# DC950TestSystem.net
KiCad netlist of a schematic drawn in EAGLE
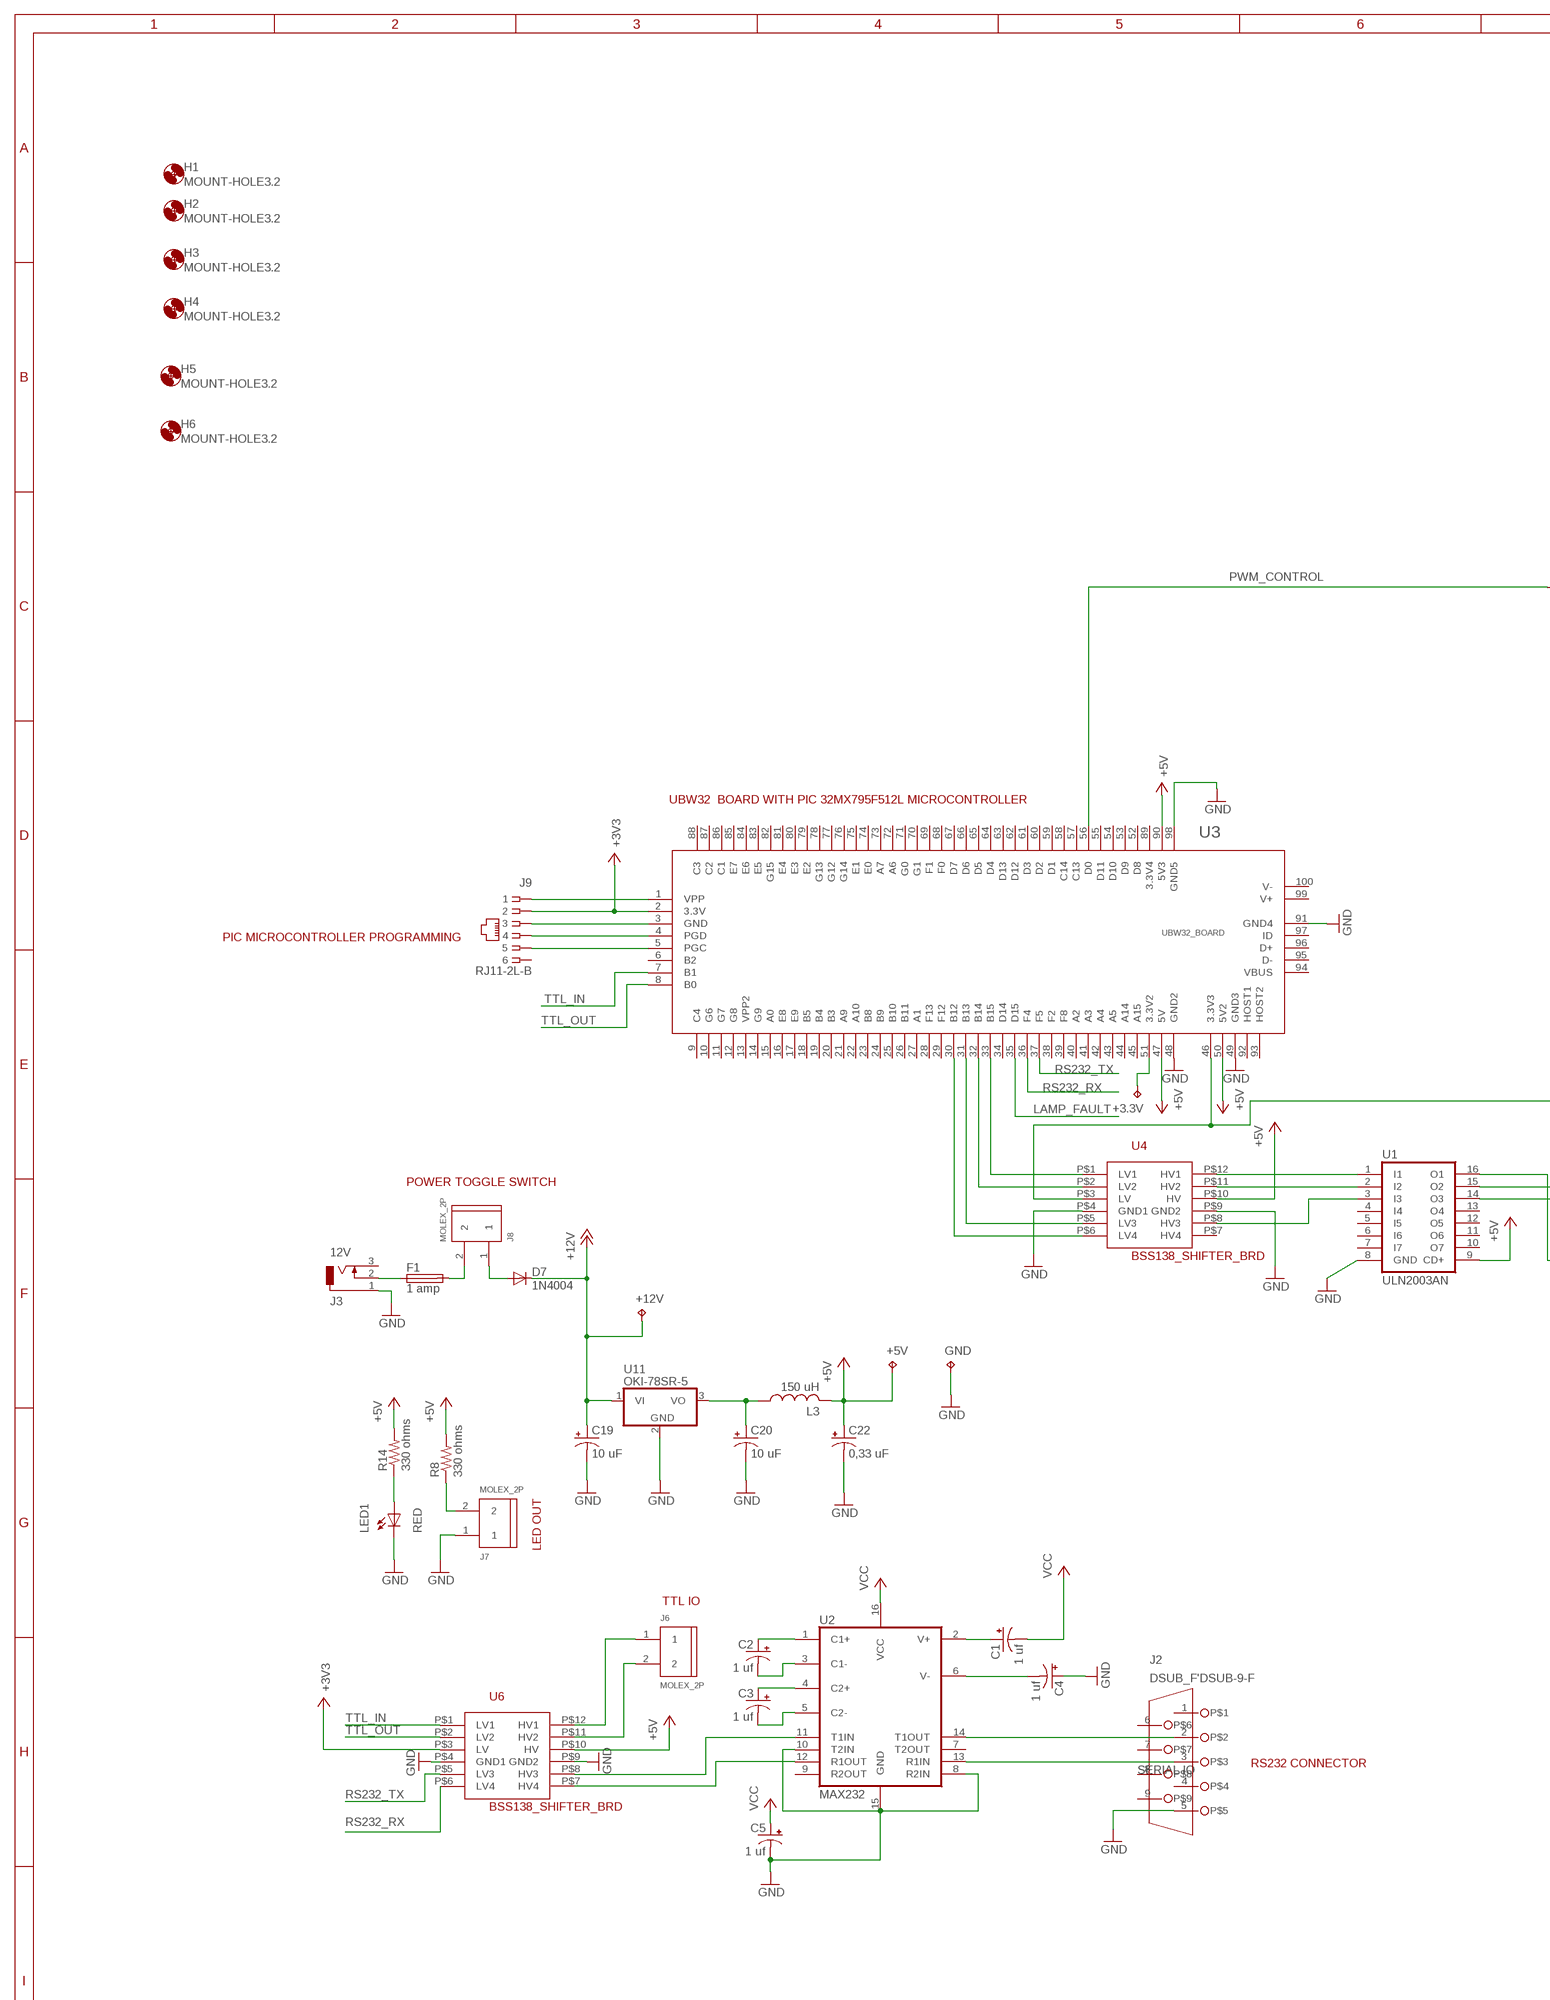
[diagram p0: schematic, sheet 1, part 1 of 2]
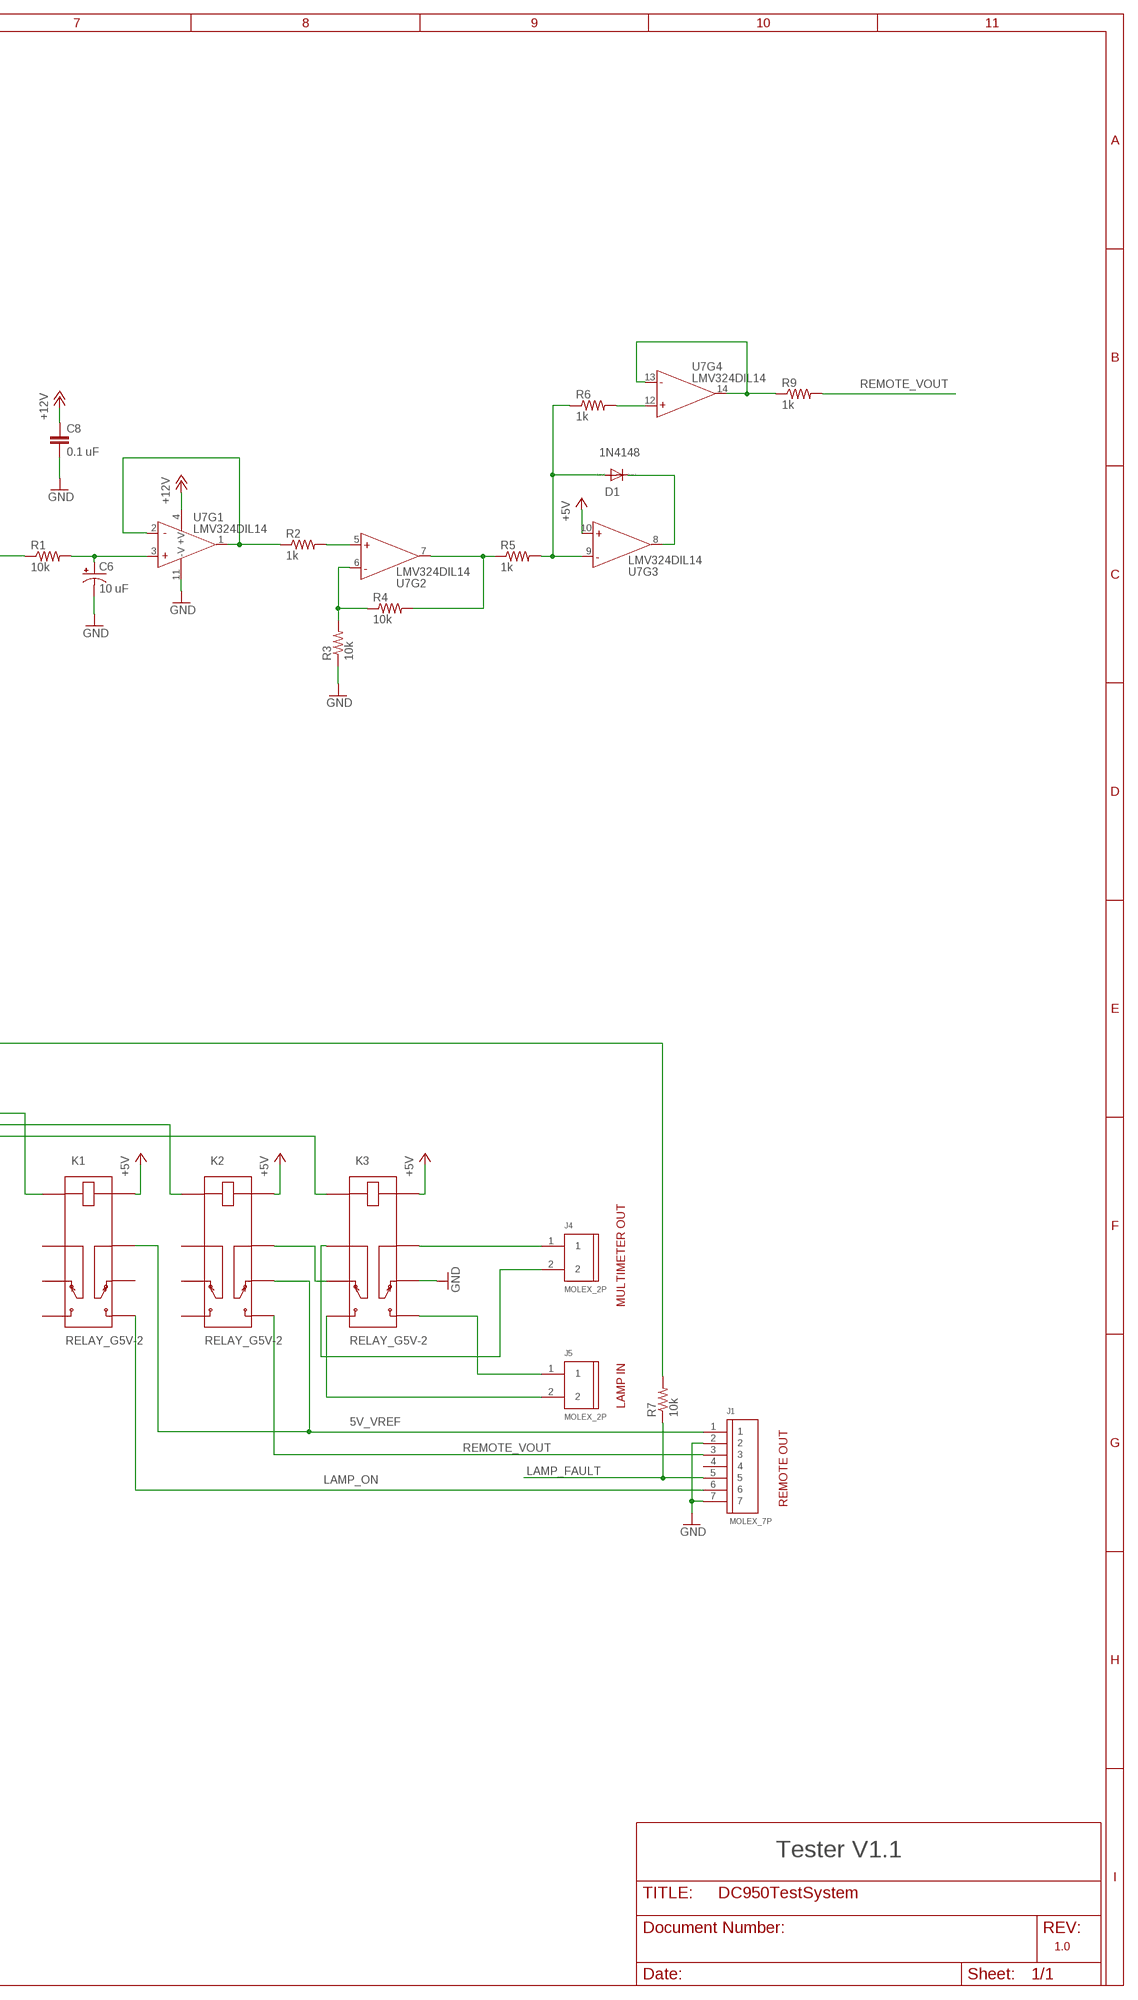
[diagram p1: schematic, sheet 1, part 2 of 2]

(export (version "E")
  (design (tool "Eeschema 10.0.6"))
  (components
    (comp (ref "+3.3V")
      (value "TP")
      (footprint "eagle-import:TESTPAD")
      (libsource (lib "eagle-import") (part "TP"))
    )
    (comp (ref "+5V")
      (value "TP")
      (footprint "eagle-import:TESTPAD")
      (libsource (lib "eagle-import") (part "TP"))
    )
    (comp (ref "+12V")
      (value "TP")
      (footprint "eagle-import:TESTPAD")
      (libsource (lib "eagle-import") (part "TP"))
    )
    (comp (ref "C1")
      (value "1 uf")
      (footprint "eagle-import:E2-5")
      (libsource (lib "eagle-import") (part "CPOL-USE2-5"))
    )
    (comp (ref "C2")
      (value "1 uf")
      (footprint "eagle-import:E2-5")
      (libsource (lib "eagle-import") (part "CPOL-USE2-5"))
    )
    (comp (ref "C3")
      (value "1 uf")
      (footprint "eagle-import:E2-5")
      (libsource (lib "eagle-import") (part "CPOL-USE2-5"))
    )
    (comp (ref "C4")
      (value "1 uf")
      (footprint "eagle-import:E2-5")
      (libsource (lib "eagle-import") (part "CPOL-USE2-5"))
    )
    (comp (ref "C5")
      (value "1 uf")
      (footprint "eagle-import:E2-5")
      (libsource (lib "eagle-import") (part "CPOL-USE2-5"))
    )
    (comp (ref "C6")
      (value "10 uF")
      (footprint "eagle-import:E2-5")
      (libsource (lib "eagle-import") (part "CPOL-USE2-5"))
    )
    (comp (ref "C8")
      (value "0.1 uF")
      (footprint "eagle-import:C5B2.5")
      (libsource (lib "eagle-import") (part "C5/2.5"))
    )
    (comp (ref "C19")
      (value "10 uF")
      (footprint "eagle-import:E2-5")
      (libsource (lib "eagle-import") (part "CPOL-USE2-5"))
    )
    (comp (ref "C20")
      (value "10 uF")
      (footprint "eagle-import:E2-5")
      (libsource (lib "eagle-import") (part "CPOL-USE2-5"))
    )
    (comp (ref "C22")
      (value "0,33 uF")
      (footprint "eagle-import:E2-5")
      (libsource (lib "eagle-import") (part "CPOL-USE2-5"))
    )
    (comp (ref "D1")
      (value "1N4148")
      (footprint "eagle-import:DO35-10")
      (libsource (lib "eagle-import") (part "1N4148DO35-10"))
    )
    (comp (ref "D7")
      (value "1N4004")
      (footprint "eagle-import:DO41-10")
      (libsource (lib "eagle-import") (part "1N4004"))
    )
    (comp (ref "F1")
      (value "1 amp")
      (footprint "eagle-import:SH22,5")
      (fields (field (name "MF") "SCHURTER") (field (name "MPN") "0031.8201"))
      (libsource (lib "eagle-import") (part "SH22,5"))
    )
    (comp (ref "GND")
      (value "TP")
      (footprint "eagle-import:TESTPAD")
      (libsource (lib "eagle-import") (part "TP"))
    )
    (comp (ref "H1")
      (value "MOUNT-HOLE3.2")
      (footprint "eagle-import:3,2")
      (libsource (lib "eagle-import") (part "MOUNT-HOLE3.2"))
    )
    (comp (ref "H2")
      (value "MOUNT-HOLE3.2")
      (footprint "eagle-import:3,2")
      (libsource (lib "eagle-import") (part "MOUNT-HOLE3.2"))
    )
    (comp (ref "H3")
      (value "MOUNT-HOLE3.2")
      (footprint "eagle-import:3,2")
      (libsource (lib "eagle-import") (part "MOUNT-HOLE3.2"))
    )
    (comp (ref "H4")
      (value "MOUNT-HOLE3.2")
      (footprint "eagle-import:3,2")
      (libsource (lib "eagle-import") (part "MOUNT-HOLE3.2"))
    )
    (comp (ref "H5")
      (value "MOUNT-HOLE3.2")
      (footprint "eagle-import:3,2")
      (libsource (lib "eagle-import") (part "MOUNT-HOLE3.2"))
    )
    (comp (ref "H6")
      (value "MOUNT-HOLE3.2")
      (footprint "eagle-import:3,2")
      (libsource (lib "eagle-import") (part "MOUNT-HOLE3.2"))
    )
    (comp (ref "J1")
      (value "MOLEX_7P")
      (footprint "eagle-import:MOLEX_7P")
      (libsource (lib "eagle-import") (part "MOLEX_7P"))
    )
    (comp (ref "J2")
      (value "DSUB_F'DSUB-9-F")
      (footprint "eagle-import:H5M09RA")
      (libsource (lib "eagle-import") (part "DSUB_F'DSUB-9-F"))
    )
    (comp (ref "J3")
      (value "12V")
      (footprint "eagle-import:DCJ0303")
      (libsource (lib "eagle-import") (part "DCJ0303"))
    )
    (comp (ref "J4")
      (value "MOLEX_2P")
      (footprint "eagle-import:MOLEX_2P")
      (libsource (lib "eagle-import") (part "MOLEX_2P"))
    )
    (comp (ref "J5")
      (value "MOLEX_2P")
      (footprint "eagle-import:MOLEX_2P")
      (libsource (lib "eagle-import") (part "MOLEX_2P"))
    )
    (comp (ref "J6")
      (value "MOLEX_2P")
      (footprint "eagle-import:MOLEX_2P")
      (libsource (lib "eagle-import") (part "MOLEX_2P"))
    )
    (comp (ref "J7")
      (value "MOLEX_2P")
      (footprint "eagle-import:MOLEX_2P")
      (libsource (lib "eagle-import") (part "MOLEX_2P"))
    )
    (comp (ref "J8")
      (value "MOLEX_2P")
      (footprint "eagle-import:MOLEX_2P")
      (libsource (lib "eagle-import") (part "MOLEX_2P"))
    )
    (comp (ref "J9")
      (value "RJ11-2L-B")
      (footprint "eagle-import:RJ11-NO_SHIELD")
      (fields (field (name "MF") "TYCO ELECTRONICS"))
      (libsource (lib "eagle-import") (part "RJ11-2L-B"))
    )
    (comp (ref "K1")
      (value "RELAY_G5V-2")
      (footprint "eagle-import:RELAY_G5V-2")
      (libsource (lib "eagle-import") (part "RELAY_G5V-2"))
    )
    (comp (ref "K2")
      (value "RELAY_G5V-2")
      (footprint "eagle-import:RELAY_G5V-2")
      (libsource (lib "eagle-import") (part "RELAY_G5V-2"))
    )
    (comp (ref "K3")
      (value "RELAY_G5V-2")
      (footprint "eagle-import:RELAY_G5V-2")
      (libsource (lib "eagle-import") (part "RELAY_G5V-2"))
    )
    (comp (ref "L3")
      (value "150 uH")
      (footprint "eagle-import:0204_7")
      (libsource (lib "eagle-import") (part "L-US0204/7"))
    )
    (comp (ref "LED1")
      (value "RED")
      (footprint "eagle-import:LED5MM")
      (libsource (lib "eagle-import") (part "LED5MM"))
    )
    (comp (ref "R1")
      (value "10k")
      (footprint "eagle-import:1_4_WATT")
      (libsource (lib "eagle-import") (part "RESISTOR0207/12"))
    )
    (comp (ref "R2")
      (value "1k")
      (footprint "eagle-import:1_4_WATT")
      (libsource (lib "eagle-import") (part "RESISTOR0207/12"))
    )
    (comp (ref "R3")
      (value "10k")
      (footprint "eagle-import:1_4_WATT")
      (libsource (lib "eagle-import") (part "RESISTOR0207/12"))
    )
    (comp (ref "R4")
      (value "10k")
      (footprint "eagle-import:1_4_WATT")
      (libsource (lib "eagle-import") (part "RESISTOR0207/12"))
    )
    (comp (ref "R5")
      (value "1k")
      (footprint "eagle-import:1_4_WATT")
      (libsource (lib "eagle-import") (part "RESISTOR0207/12"))
    )
    (comp (ref "R6")
      (value "1k")
      (footprint "eagle-import:1_4_WATT")
      (libsource (lib "eagle-import") (part "RESISTOR0207/12"))
    )
    (comp (ref "R7")
      (value "10k")
      (footprint "eagle-import:1_4_WATT")
      (libsource (lib "eagle-import") (part "RESISTOR0207/12"))
    )
    (comp (ref "R8")
      (value "330 ohms")
      (footprint "eagle-import:0207_10")
      (libsource (lib "eagle-import") (part "R-US_0207/10"))
    )
    (comp (ref "R9")
      (value "1k")
      (footprint "eagle-import:1_4_WATT")
      (libsource (lib "eagle-import") (part "RESISTOR0207/12"))
    )
    (comp (ref "R14")
      (value "330 ohms")
      (footprint "eagle-import:0207_10")
      (libsource (lib "eagle-import") (part "R-US_0207/10"))
    )
    (comp (ref "U1")
      (value "ULN2003AN")
      (footprint "eagle-import:DIL16")
      (libsource (lib "eagle-import") (part "ULN2003AN"))
    )
    (comp (ref "U2")
      (value "MAX232")
      (footprint "eagle-import:DIL16")
      (fields (field (name "MF") "MAXIM") (field (name "MPN") "MAX232ACPE+"))
      (libsource (lib "eagle-import") (part "MAX232"))
    )
    (comp (ref "U3")
      (value "UBW32_BOARD")
      (footprint "eagle-import:UBW32")
      (libsource (lib "eagle-import") (part "UBW32_BOARD"))
    )
    (comp (ref "U4")
      (value "BSS138_SHIFTER_BRD")
      (footprint "eagle-import:BSS138_SHIFTER_BRD")
      (libsource (lib "eagle-import") (part "BSS138_SHIFTER_BRD"))
    )
    (comp (ref "U6")
      (value "BSS138_SHIFTER_BRD")
      (footprint "eagle-import:BSS138_SHIFTER_BRD")
      (libsource (lib "eagle-import") (part "BSS138_SHIFTER_BRD"))
    )
    (comp (ref "U7")
      (value "LMV324DIL14")
      (footprint "eagle-import:DIL14")
      (libsource (lib "eagle-import") (part "LMV324DIL14"))
    )
    (comp (ref "U11")
      (value "OKI-78SR-5")
      (footprint "eagle-import:TO220V")
      (libsource (lib "eagle-import") (part "78TV05"))
    )
  )
  (nets
    (net (code "1") (name "+3V3") (class "Default")
      (node (ref "J9") (pin "2") (pinfunction "2_2") (pintype "passive"))
      (node (ref "U3") (pin "2") (pinfunction "3.3V_2") (pintype "power_in"))
      (node (ref "U6") (pin "P$3") (pinfunction "LV_P$3") (pintype "bidirectional"))
    )
    (net (code "2") (name "+5V") (class "Default")
      (node (ref "+5V") (pin "P$1") (pinfunction "TP_P$1") (pintype "input"))
      (node (ref "C22") (pin "+") (pinfunction "+_+") (pintype "passive"))
      (node (ref "K1") (pin "16") (pinfunction "16_16") (pintype "bidirectional"))
      (node (ref "K2") (pin "16") (pinfunction "16_16") (pintype "bidirectional"))
      (node (ref "K3") (pin "16") (pinfunction "16_16") (pintype "bidirectional"))
      (node (ref "L3") (pin "2") (pinfunction "2_2") (pintype "passive"))
      (node (ref "R14") (pin "2") (pinfunction "2_2") (pintype "passive"))
      (node (ref "R8") (pin "2") (pinfunction "2_2") (pintype "passive"))
      (node (ref "U1") (pin "9") (pinfunction "CD+_9") (pintype "passive"))
      (node (ref "U3") (pin "47") (pinfunction "5V_47") (pintype "power_in"))
      (node (ref "U3") (pin "50") (pinfunction "5V2_50") (pintype "power_in"))
      (node (ref "U3") (pin "90") (pinfunction "5V3_90") (pintype "power_in"))
      (node (ref "U4") (pin "P$10") (pinfunction "HV_P$10") (pintype "bidirectional"))
      (node (ref "U6") (pin "P$10") (pinfunction "HV_P$10") (pintype "bidirectional"))
      (node (ref "U7") (pin "10") (pinfunction "+IN_10") (pintype "input"))
    )
    (net (code "3") (name "+12V") (class "Default")
      (node (ref "+12V") (pin "P$1") (pinfunction "TP_P$1") (pintype "input"))
      (node (ref "C19") (pin "+") (pinfunction "+_+") (pintype "passive"))
      (node (ref "C8") (pin "1") (pinfunction "1_1") (pintype "passive"))
      (node (ref "D7") (pin "C") (pinfunction "C_C") (pintype "passive"))
      (node (ref "U11") (pin "1") (pinfunction "VI_1") (pintype "input"))
      (node (ref "U7") (pin "4") (pinfunction "+V_4") (pintype "power_in"))
    )
    (net (code "4") (name "/3.3V4") (class "Default")
      (node (ref "U3") (pin "89") (pinfunction "3.3V4_89") (pintype "power_in"))
    )
    (net (code "5") (name "/5V_VREF") (class "Default")
      (node (ref "J1") (pin "1") (pinfunction "1_1") (pintype "bidirectional"))
      (node (ref "K1") (pin "13") (pinfunction "13_13") (pintype "bidirectional"))
      (node (ref "K2") (pin "11") (pinfunction "11_11") (pintype "bidirectional"))
    )
    (net (code "6") (name "/LAMP_FAULT") (class "Default")
      (node (ref "J1") (pin "5") (pinfunction "5_5") (pintype "bidirectional"))
      (node (ref "R7") (pin "1") (pinfunction "1_1") (pintype "passive"))
      (node (ref "U3") (pin "35") (pinfunction "D15_35") (pintype "bidirectional"))
    )
    (net (code "7") (name "/LAMP_ON") (class "Default")
      (node (ref "J1") (pin "6") (pinfunction "6_6") (pintype "bidirectional"))
      (node (ref "K1") (pin "9") (pinfunction "9_9") (pintype "bidirectional"))
    )
    (net (code "8") (name "/PWM_CONTROL") (class "Default")
      (node (ref "R1") (pin "1") (pinfunction "1_1") (pintype "passive"))
      (node (ref "U3") (pin "56") (pinfunction "D0_56") (pintype "bidirectional"))
    )
    (net (code "9") (name "/REMOTE_VOUT") (class "Default")
      (node (ref "J1") (pin "3") (pinfunction "3_3") (pintype "bidirectional"))
      (node (ref "K2") (pin "9") (pinfunction "9_9") (pintype "bidirectional"))
      (node (ref "R9") (pin "2") (pinfunction "2_2") (pintype "passive"))
    )
    (net (code "10") (name "/RS232_RX") (class "Default")
      (node (ref "U3") (pin "36") (pinfunction "F4_36") (pintype "bidirectional"))
      (node (ref "U6") (pin "P$6") (pinfunction "LV4_P$6") (pintype "bidirectional"))
    )
    (net (code "11") (name "/RS232_TX") (class "Default")
      (node (ref "U3") (pin "37") (pinfunction "F5_37") (pintype "bidirectional"))
      (node (ref "U6") (pin "P$5") (pinfunction "LV3_P$5") (pintype "bidirectional"))
    )
    (net (code "12") (name "/TTL_IN") (class "Default")
      (node (ref "U3") (pin "7") (pinfunction "B1_7") (pintype "bidirectional"))
      (node (ref "U6") (pin "P$1") (pinfunction "LV1_P$1") (pintype "bidirectional"))
    )
    (net (code "13") (name "/TTL_OUT") (class "Default")
      (node (ref "U3") (pin "8") (pinfunction "B0_8") (pintype "bidirectional"))
      (node (ref "U6") (pin "P$2") (pinfunction "LV2_P$2") (pintype "bidirectional"))
    )
    (net (code "14") (name "/V+") (class "Default")
      (node (ref "U3") (pin "99") (pinfunction "V+_99") (pintype "power_in"))
    )
    (net (code "15") (name "/V-") (class "Default")
      (node (ref "U3") (pin "100") (pinfunction "V-_100") (pintype "power_in"))
    )
    (net (code "16") (name "/VBUS") (class "Default")
      (node (ref "U3") (pin "94") (pinfunction "VBUS_94") (pintype "power_in"))
    )
    (net (code "17") (name "GND") (class "Default")
      (node (ref "C19") (pin "-") (pinfunction "-_-") (pintype "passive"))
      (node (ref "C20") (pin "-") (pinfunction "-_-") (pintype "passive"))
      (node (ref "C22") (pin "-") (pinfunction "-_-") (pintype "passive"))
      (node (ref "C4") (pin "+") (pinfunction "+_+") (pintype "passive"))
      (node (ref "C5") (pin "-") (pinfunction "-_-") (pintype "passive"))
      (node (ref "C6") (pin "-") (pinfunction "-_-") (pintype "passive"))
      (node (ref "C8") (pin "2") (pinfunction "2_2") (pintype "passive"))
      (node (ref "GND") (pin "P$1") (pinfunction "TP_P$1") (pintype "input"))
      (node (ref "J1") (pin "2") (pinfunction "2_2") (pintype "bidirectional"))
      (node (ref "J1") (pin "7") (pinfunction "7_7") (pintype "bidirectional"))
      (node (ref "J2") (pin "5") (pinfunction "P$5_5") (pintype "bidirectional"))
      (node (ref "J3") (pin "1") (pinfunction "1_1") (pintype "passive"))
      (node (ref "J7") (pin "1") (pinfunction "1_1") (pintype "bidirectional"))
      (node (ref "K3") (pin "11") (pinfunction "11_11") (pintype "bidirectional"))
      (node (ref "LED1") (pin "K") (pinfunction "C_K") (pintype "passive"))
      (node (ref "R3") (pin "1") (pinfunction "1_1") (pintype "passive"))
      (node (ref "U1") (pin "8") (pinfunction "GND_8") (pintype "power_in"))
      (node (ref "U11") (pin "2") (pinfunction "GND_2") (pintype "passive"))
      (node (ref "U2") (pin "10") (pinfunction "T2IN_10") (pintype "input"))
      (node (ref "U2") (pin "15") (pinfunction "GND_15") (pintype "bidirectional"))
      (node (ref "U2") (pin "8") (pinfunction "R2IN_8") (pintype "input"))
      (node (ref "U3") (pin "48") (pinfunction "GND2_48") (pintype "power_in"))
      (node (ref "U3") (pin "49") (pinfunction "GND3_49") (pintype "power_in"))
      (node (ref "U3") (pin "91") (pinfunction "GND4_91") (pintype "power_in"))
      (node (ref "U3") (pin "98") (pinfunction "GND5_98") (pintype "power_in"))
      (node (ref "U4") (pin "P$4") (pinfunction "GND1_P$4") (pintype "bidirectional"))
      (node (ref "U4") (pin "P$9") (pinfunction "GND2_P$9") (pintype "bidirectional"))
      (node (ref "U6") (pin "P$4") (pinfunction "GND1_P$4") (pintype "bidirectional"))
      (node (ref "U6") (pin "P$9") (pinfunction "GND2_P$9") (pintype "bidirectional"))
      (node (ref "U7") (pin "11") (pinfunction "-V_11") (pintype "power_in"))
    )
    (net (code "18") (name "Net-(+3.3V-TP)") (class "Default")
      (node (ref "+3.3V") (pin "P$1") (pinfunction "TP_P$1") (pintype "input"))
      (node (ref "U3") (pin "51") (pinfunction "3.3V2_51") (pintype "power_in"))
    )
    (net (code "19") (name "Net-(D7-PadA)") (class "Default")
      (node (ref "D7") (pin "A") (pinfunction "A_A") (pintype "passive"))
      (node (ref "J8") (pin "1") (pinfunction "1_1") (pintype "bidirectional"))
    )
    (net (code "20") (name "Net-(F1-Pad1)") (class "Default")
      (node (ref "F1") (pin "1") (pinfunction "1_1") (pintype "passive"))
      (node (ref "J3") (pin "2") (pinfunction "2_2") (pintype "passive"))
    )
    (net (code "21") (name "Net-(F1-Pad2)") (class "Default")
      (node (ref "F1") (pin "2") (pinfunction "2_2") (pintype "passive"))
      (node (ref "J8") (pin "2") (pinfunction "2_2") (pintype "bidirectional"))
    )
    (net (code "22") (name "Net-(J2-P$2)") (class "Default")
      (node (ref "J2") (pin "2") (pinfunction "P$2_2") (pintype "bidirectional"))
      (node (ref "U2") (pin "14") (pinfunction "T1OUT_14") (pintype "output"))
    )
    (net (code "23") (name "Net-(J2-P$3)") (class "Default")
      (node (ref "J2") (pin "3") (pinfunction "P$3_3") (pintype "bidirectional"))
      (node (ref "U2") (pin "13") (pinfunction "R1IN_13") (pintype "input"))
    )
    (net (code "24") (name "Net-(J4-Pad1)") (class "Default")
      (node (ref "J4") (pin "1") (pinfunction "1_1") (pintype "bidirectional"))
      (node (ref "K3") (pin "13") (pinfunction "13_13") (pintype "bidirectional"))
    )
    (net (code "25") (name "Net-(J4-Pad2)") (class "Default")
      (node (ref "J4") (pin "2") (pinfunction "2_2") (pintype "bidirectional"))
      (node (ref "K3") (pin "4") (pinfunction "4_4") (pintype "bidirectional"))
    )
    (net (code "26") (name "Net-(J5-Pad1)") (class "Default")
      (node (ref "J5") (pin "1") (pinfunction "1_1") (pintype "bidirectional"))
      (node (ref "K3") (pin "9") (pinfunction "9_9") (pintype "bidirectional"))
    )
    (net (code "27") (name "Net-(J5-Pad2)") (class "Default")
      (node (ref "J5") (pin "2") (pinfunction "2_2") (pintype "bidirectional"))
      (node (ref "K3") (pin "8") (pinfunction "8_8") (pintype "bidirectional"))
    )
    (net (code "28") (name "Net-(J7-Pad2)") (class "Default")
      (node (ref "J7") (pin "2") (pinfunction "2_2") (pintype "bidirectional"))
      (node (ref "R8") (pin "1") (pinfunction "1_1") (pintype "passive"))
    )
    (net (code "29") (name "Net-(K2-Pad13)") (class "Default")
      (node (ref "K2") (pin "13") (pinfunction "13_13") (pintype "bidirectional"))
      (node (ref "K3") (pin "6") (pinfunction "6_6") (pintype "bidirectional"))
    )
    (net (code "30") (name "Net-(LED1-PadA)") (class "Default")
      (node (ref "LED1") (pin "A") (pinfunction "A_A") (pintype "passive"))
      (node (ref "R14") (pin "1") (pinfunction "1_1") (pintype "passive"))
    )
    (net (code "31") (name "Net-(U1-I1)") (class "Default")
      (node (ref "U1") (pin "1") (pinfunction "I1_1") (pintype "input"))
      (node (ref "U4") (pin "P$12") (pinfunction "HV1_P$12") (pintype "bidirectional"))
    )
    (net (code "32") (name "Net-(U1-I2)") (class "Default")
      (node (ref "U1") (pin "2") (pinfunction "I2_2") (pintype "input"))
      (node (ref "U4") (pin "P$11") (pinfunction "HV2_P$11") (pintype "bidirectional"))
    )
    (net (code "33") (name "Net-(U1-I3)") (class "Default")
      (node (ref "U1") (pin "3") (pinfunction "I3_3") (pintype "input"))
      (node (ref "U4") (pin "P$8") (pinfunction "HV3_P$8") (pintype "bidirectional"))
    )
    (net (code "34") (name "Net-(U1-O1)") (class "Default")
      (node (ref "K1") (pin "1") (pinfunction "1_1") (pintype "bidirectional"))
      (node (ref "U1") (pin "16") (pinfunction "O1_16") (pintype "open_collector"))
    )
    (net (code "35") (name "Net-(U1-O2)") (class "Default")
      (node (ref "K2") (pin "1") (pinfunction "1_1") (pintype "bidirectional"))
      (node (ref "U1") (pin "15") (pinfunction "O2_15") (pintype "open_collector"))
    )
    (net (code "36") (name "Net-(U1-O3)") (class "Default")
      (node (ref "K3") (pin "1") (pinfunction "1_1") (pintype "bidirectional"))
      (node (ref "U1") (pin "14") (pinfunction "O3_14") (pintype "open_collector"))
    )
    (net (code "37") (name "Net-(U2-C1+)") (class "Default")
      (node (ref "C2") (pin "+") (pinfunction "+_+") (pintype "passive"))
      (node (ref "U2") (pin "1") (pinfunction "C1+_1") (pintype "bidirectional"))
    )
    (net (code "38") (name "Net-(U2-C1-)") (class "Default")
      (node (ref "C2") (pin "-") (pinfunction "-_-") (pintype "passive"))
      (node (ref "U2") (pin "3") (pinfunction "C1-_3") (pintype "bidirectional"))
    )
    (net (code "39") (name "Net-(U2-C2+)") (class "Default")
      (node (ref "C3") (pin "+") (pinfunction "+_+") (pintype "passive"))
      (node (ref "U2") (pin "4") (pinfunction "C2+_4") (pintype "bidirectional"))
    )
    (net (code "40") (name "Net-(U2-C2-)") (class "Default")
      (node (ref "C3") (pin "-") (pinfunction "-_-") (pintype "passive"))
      (node (ref "U2") (pin "5") (pinfunction "C2-_5") (pintype "bidirectional"))
    )
    (net (code "41") (name "Net-(U2-R1OUT)") (class "Default")
      (node (ref "U2") (pin "12") (pinfunction "R1OUT_12") (pintype "output"))
      (node (ref "U6") (pin "P$7") (pinfunction "HV4_P$7") (pintype "bidirectional"))
    )
    (net (code "42") (name "Net-(U2-T1IN)") (class "Default")
      (node (ref "U2") (pin "11") (pinfunction "T1IN_11") (pintype "input"))
      (node (ref "U6") (pin "P$8") (pinfunction "HV3_P$8") (pintype "bidirectional"))
    )
    (net (code "43") (name "Net-(U2-V+)") (class "Default")
      (node (ref "C1") (pin "+") (pinfunction "+_+") (pintype "passive"))
      (node (ref "U2") (pin "2") (pinfunction "V+_2") (pintype "bidirectional"))
    )
    (net (code "44") (name "Net-(U2-V-)") (class "Default")
      (node (ref "C4") (pin "-") (pinfunction "-_-") (pintype "passive"))
      (node (ref "U2") (pin "6") (pinfunction "V-_6") (pintype "bidirectional"))
    )
    (net (code "45") (name "Net-(U3-3.3V3)") (class "Default")
      (node (ref "R7") (pin "2") (pinfunction "2_2") (pintype "passive"))
      (node (ref "U3") (pin "46") (pinfunction "3.3V3_46") (pintype "power_in"))
      (node (ref "U4") (pin "P$3") (pinfunction "LV_P$3") (pintype "bidirectional"))
    )
    (net (code "46") (name "Net-(U3-B12)") (class "Default")
      (node (ref "U3") (pin "30") (pinfunction "B12_30") (pintype "bidirectional"))
      (node (ref "U4") (pin "P$6") (pinfunction "LV4_P$6") (pintype "bidirectional"))
    )
    (net (code "47") (name "Net-(U3-B13)") (class "Default")
      (node (ref "U3") (pin "31") (pinfunction "B13_31") (pintype "bidirectional"))
      (node (ref "U4") (pin "P$5") (pinfunction "LV3_P$5") (pintype "bidirectional"))
    )
    (net (code "48") (name "Net-(U3-B14)") (class "Default")
      (node (ref "U3") (pin "32") (pinfunction "B14_32") (pintype "bidirectional"))
      (node (ref "U4") (pin "P$2") (pinfunction "LV2_P$2") (pintype "bidirectional"))
    )
    (net (code "49") (name "Net-(U3-B15)") (class "Default")
      (node (ref "U3") (pin "33") (pinfunction "B15_33") (pintype "bidirectional"))
      (node (ref "U4") (pin "P$1") (pinfunction "LV1_P$1") (pintype "bidirectional"))
    )
    (net (code "50") (name "Net-(U3-GND)") (class "Default")
      (node (ref "J9") (pin "3") (pinfunction "3_3") (pintype "passive"))
      (node (ref "U3") (pin "3") (pinfunction "GND_3") (pintype "power_in"))
    )
    (net (code "51") (name "Net-(U3-PGC)") (class "Default")
      (node (ref "J9") (pin "5") (pinfunction "5_5") (pintype "passive"))
      (node (ref "U3") (pin "5") (pinfunction "PGC_5") (pintype "bidirectional"))
    )
    (net (code "52") (name "Net-(U3-PGD)") (class "Default")
      (node (ref "J9") (pin "4") (pinfunction "4_4") (pintype "passive"))
      (node (ref "U3") (pin "4") (pinfunction "PGD_4") (pintype "bidirectional"))
    )
    (net (code "53") (name "Net-(U3-VPP)") (class "Default")
      (node (ref "J9") (pin "1") (pinfunction "1_1") (pintype "passive"))
      (node (ref "U3") (pin "1") (pinfunction "VPP_1") (pintype "input"))
    )
    (net (code "54") (name "Net-(U6-HV1)") (class "Default")
      (node (ref "J6") (pin "1") (pinfunction "1_1") (pintype "bidirectional"))
      (node (ref "U6") (pin "P$12") (pinfunction "HV1_P$12") (pintype "bidirectional"))
    )
    (net (code "55") (name "Net-(U6-HV2)") (class "Default")
      (node (ref "J6") (pin "2") (pinfunction "2_2") (pintype "bidirectional"))
      (node (ref "U6") (pin "P$11") (pinfunction "HV2_P$11") (pintype "bidirectional"))
    )
    (net (code "56") (name "Net-(U7A-+IN)") (class "Default")
      (node (ref "C6") (pin "+") (pinfunction "+_+") (pintype "passive"))
      (node (ref "R1") (pin "2") (pinfunction "2_2") (pintype "passive"))
      (node (ref "U7") (pin "3") (pinfunction "+IN_3") (pintype "input"))
    )
    (net (code "57") (name "Net-(U7A--IN)") (class "Default")
      (node (ref "R2") (pin "1") (pinfunction "1_1") (pintype "passive"))
      (node (ref "U7") (pin "1") (pinfunction "OUT_1") (pintype "output"))
      (node (ref "U7") (pin "2") (pinfunction "-IN_2") (pintype "input"))
    )
    (net (code "58") (name "Net-(U7B-+IN)") (class "Default")
      (node (ref "R2") (pin "2") (pinfunction "2_2") (pintype "passive"))
      (node (ref "U7") (pin "5") (pinfunction "+IN_5") (pintype "input"))
    )
    (net (code "59") (name "Net-(U7B--IN)") (class "Default")
      (node (ref "R3") (pin "2") (pinfunction "2_2") (pintype "passive"))
      (node (ref "R4") (pin "1") (pinfunction "1_1") (pintype "passive"))
      (node (ref "U7") (pin "6") (pinfunction "-IN_6") (pintype "input"))
    )
    (net (code "60") (name "Net-(U7B-OUT)") (class "Default")
      (node (ref "R4") (pin "2") (pinfunction "2_2") (pintype "passive"))
      (node (ref "R5") (pin "1") (pinfunction "1_1") (pintype "passive"))
      (node (ref "U7") (pin "7") (pinfunction "OUT_7") (pintype "output"))
    )
    (net (code "61") (name "Net-(U7C--IN)") (class "Default")
      (node (ref "D1") (pin "A") (pinfunction "A_A") (pintype "passive"))
      (node (ref "R5") (pin "2") (pinfunction "2_2") (pintype "passive"))
      (node (ref "R6") (pin "1") (pinfunction "1_1") (pintype "passive"))
      (node (ref "U7") (pin "9") (pinfunction "-IN_9") (pintype "input"))
    )
    (net (code "62") (name "Net-(U7C-OUT)") (class "Default")
      (node (ref "D1") (pin "C") (pinfunction "C_C") (pintype "passive"))
      (node (ref "U7") (pin "8") (pinfunction "OUT_8") (pintype "output"))
    )
    (net (code "63") (name "Net-(U7D-+IN)") (class "Default")
      (node (ref "R6") (pin "2") (pinfunction "2_2") (pintype "passive"))
      (node (ref "U7") (pin "12") (pinfunction "+IN_12") (pintype "input"))
    )
    (net (code "64") (name "Net-(U7D--IN)") (class "Default")
      (node (ref "R9") (pin "1") (pinfunction "1_1") (pintype "passive"))
      (node (ref "U7") (pin "13") (pinfunction "-IN_13") (pintype "input"))
      (node (ref "U7") (pin "14") (pinfunction "OUT_14") (pintype "output"))
    )
    (net (code "65") (name "Net-(U11-VO)") (class "Default")
      (node (ref "C20") (pin "+") (pinfunction "+_+") (pintype "passive"))
      (node (ref "L3") (pin "1") (pinfunction "1_1") (pintype "passive"))
      (node (ref "U11") (pin "3") (pinfunction "VO_3") (pintype "passive"))
    )
    (net (code "66") (name "VCC") (class "Default")
      (node (ref "C1") (pin "-") (pinfunction "-_-") (pintype "passive"))
      (node (ref "C5") (pin "+") (pinfunction "+_+") (pintype "passive"))
      (node (ref "U2") (pin "16") (pinfunction "VCC_16") (pintype "bidirectional"))
    )
    (net (code "67") (name "unconnected-(J1-Pad4)") (class "Default")
      (node (ref "J1") (pin "4") (pinfunction "4_4") (pintype "bidirectional"))
    )
    (net (code "68") (name "unconnected-(J2-P$1-Pad1)") (class "Default")
      (node (ref "J2") (pin "1") (pinfunction "P$1_1") (pintype "bidirectional"))
    )
    (net (code "69") (name "unconnected-(J2-P$4-Pad4)") (class "Default")
      (node (ref "J2") (pin "4") (pinfunction "P$4_4") (pintype "bidirectional"))
    )
    (net (code "70") (name "unconnected-(J2-P$6-Pad6)") (class "Default")
      (node (ref "J2") (pin "6") (pinfunction "P$6_6") (pintype "bidirectional"))
    )
    (net (code "71") (name "unconnected-(J2-P$7-Pad7)") (class "Default")
      (node (ref "J2") (pin "7") (pinfunction "P$7_7") (pintype "bidirectional"))
    )
    (net (code "72") (name "unconnected-(J2-P$8-Pad8)") (class "Default")
      (node (ref "J2") (pin "8") (pinfunction "P$8_8") (pintype "bidirectional"))
    )
    (net (code "73") (name "unconnected-(J2-P$9-Pad9)") (class "Default")
      (node (ref "J2") (pin "9") (pinfunction "P$9_9") (pintype "bidirectional"))
    )
    (net (code "74") (name "unconnected-(J3-Pad3)") (class "Default")
      (node (ref "J3") (pin "3") (pinfunction "3_3") (pintype "passive"))
    )
    (net (code "75") (name "unconnected-(J9-Pad6)") (class "Default")
      (node (ref "J9") (pin "6") (pinfunction "6_6") (pintype "passive"))
    )
    (net (code "76") (name "unconnected-(K1-Pad4)") (class "Default")
      (node (ref "K1") (pin "4") (pinfunction "4_4") (pintype "bidirectional"))
    )
    (net (code "77") (name "unconnected-(K1-Pad6)") (class "Default")
      (node (ref "K1") (pin "6") (pinfunction "6_6") (pintype "bidirectional"))
    )
    (net (code "78") (name "unconnected-(K1-Pad8)") (class "Default")
      (node (ref "K1") (pin "8") (pinfunction "8_8") (pintype "bidirectional"))
    )
    (net (code "79") (name "unconnected-(K1-Pad11)") (class "Default")
      (node (ref "K1") (pin "11") (pinfunction "11_11") (pintype "bidirectional"))
    )
    (net (code "80") (name "unconnected-(K2-Pad4)") (class "Default")
      (node (ref "K2") (pin "4") (pinfunction "4_4") (pintype "bidirectional"))
    )
    (net (code "81") (name "unconnected-(K2-Pad6)") (class "Default")
      (node (ref "K2") (pin "6") (pinfunction "6_6") (pintype "bidirectional"))
    )
    (net (code "82") (name "unconnected-(K2-Pad8)") (class "Default")
      (node (ref "K2") (pin "8") (pinfunction "8_8") (pintype "bidirectional"))
    )
    (net (code "83") (name "unconnected-(U1-I4-Pad4)") (class "Default")
      (node (ref "U1") (pin "4") (pinfunction "I4_4") (pintype "input"))
    )
    (net (code "84") (name "unconnected-(U1-I5-Pad5)") (class "Default")
      (node (ref "U1") (pin "5") (pinfunction "I5_5") (pintype "input"))
    )
    (net (code "85") (name "unconnected-(U1-I6-Pad6)") (class "Default")
      (node (ref "U1") (pin "6") (pinfunction "I6_6") (pintype "input"))
    )
    (net (code "86") (name "unconnected-(U1-I7-Pad7)") (class "Default")
      (node (ref "U1") (pin "7") (pinfunction "I7_7") (pintype "input"))
    )
    (net (code "87") (name "unconnected-(U1-O4-Pad13)") (class "Default")
      (node (ref "U1") (pin "13") (pinfunction "O4_13") (pintype "open_collector"))
    )
    (net (code "88") (name "unconnected-(U1-O5-Pad12)") (class "Default")
      (node (ref "U1") (pin "12") (pinfunction "O5_12") (pintype "open_collector"))
    )
    (net (code "89") (name "unconnected-(U1-O6-Pad11)") (class "Default")
      (node (ref "U1") (pin "11") (pinfunction "O6_11") (pintype "open_collector"))
    )
    (net (code "90") (name "unconnected-(U1-O7-Pad10)") (class "Default")
      (node (ref "U1") (pin "10") (pinfunction "O7_10") (pintype "open_collector"))
    )
    (net (code "91") (name "unconnected-(U2-R2OUT-Pad9)") (class "Default")
      (node (ref "U2") (pin "9") (pinfunction "R2OUT_9") (pintype "output"))
    )
    (net (code "92") (name "unconnected-(U2-T2OUT-Pad7)") (class "Default")
      (node (ref "U2") (pin "7") (pinfunction "T2OUT_7") (pintype "output"))
    )
    (net (code "93") (name "unconnected-(U3-A0-Pad15)") (class "Default")
      (node (ref "U3") (pin "15") (pinfunction "A0_15") (pintype "bidirectional"))
    )
    (net (code "94") (name "unconnected-(U3-A1-Pad27)") (class "Default")
      (node (ref "U3") (pin "27") (pinfunction "A1_27") (pintype "bidirectional"))
    )
    (net (code "95") (name "unconnected-(U3-A2-Pad40)") (class "Default")
      (node (ref "U3") (pin "40") (pinfunction "A2_40") (pintype "bidirectional"))
    )
    (net (code "96") (name "unconnected-(U3-A3-Pad41)") (class "Default")
      (node (ref "U3") (pin "41") (pinfunction "A3_41") (pintype "bidirectional"))
    )
    (net (code "97") (name "unconnected-(U3-A4-Pad42)") (class "Default")
      (node (ref "U3") (pin "42") (pinfunction "A4_42") (pintype "bidirectional"))
    )
    (net (code "98") (name "unconnected-(U3-A5-Pad43)") (class "Default")
      (node (ref "U3") (pin "43") (pinfunction "A5_43") (pintype "bidirectional"))
    )
    (net (code "99") (name "unconnected-(U3-A6-Pad72)") (class "Default")
      (node (ref "U3") (pin "72") (pinfunction "A6_72") (pintype "bidirectional"))
    )
    (net (code "100") (name "unconnected-(U3-A7-Pad73)") (class "Default")
      (node (ref "U3") (pin "73") (pinfunction "A7_73") (pintype "bidirectional"))
    )
    (net (code "101") (name "unconnected-(U3-A9-Pad21)") (class "Default")
      (node (ref "U3") (pin "21") (pinfunction "A9_21") (pintype "bidirectional"))
    )
    (net (code "102") (name "unconnected-(U3-A10-Pad22)") (class "Default")
      (node (ref "U3") (pin "22") (pinfunction "A10_22") (pintype "bidirectional"))
    )
    (net (code "103") (name "unconnected-(U3-A14-Pad44)") (class "Default")
      (node (ref "U3") (pin "44") (pinfunction "A14_44") (pintype "bidirectional"))
    )
    (net (code "104") (name "unconnected-(U3-A15-Pad45)") (class "Default")
      (node (ref "U3") (pin "45") (pinfunction "A15_45") (pintype "bidirectional"))
    )
    (net (code "105") (name "unconnected-(U3-B2-Pad6)") (class "Default")
      (node (ref "U3") (pin "6") (pinfunction "B2_6") (pintype "bidirectional"))
    )
    (net (code "106") (name "unconnected-(U3-B3-Pad20)") (class "Default")
      (node (ref "U3") (pin "20") (pinfunction "B3_20") (pintype "bidirectional"))
    )
    (net (code "107") (name "unconnected-(U3-B4-Pad19)") (class "Default")
      (node (ref "U3") (pin "19") (pinfunction "B4_19") (pintype "bidirectional"))
    )
    (net (code "108") (name "unconnected-(U3-B5-Pad18)") (class "Default")
      (node (ref "U3") (pin "18") (pinfunction "B5_18") (pintype "bidirectional"))
    )
    (net (code "109") (name "unconnected-(U3-B8-Pad23)") (class "Default")
      (node (ref "U3") (pin "23") (pinfunction "B8_23") (pintype "bidirectional"))
    )
    (net (code "110") (name "unconnected-(U3-B9-Pad24)") (class "Default")
      (node (ref "U3") (pin "24") (pinfunction "B9_24") (pintype "bidirectional"))
    )
    (net (code "111") (name "unconnected-(U3-B10-Pad25)") (class "Default")
      (node (ref "U3") (pin "25") (pinfunction "B10_25") (pintype "bidirectional"))
    )
    (net (code "112") (name "unconnected-(U3-B11-Pad26)") (class "Default")
      (node (ref "U3") (pin "26") (pinfunction "B11_26") (pintype "bidirectional"))
    )
    (net (code "113") (name "unconnected-(U3-C1-Pad86)") (class "Default")
      (node (ref "U3") (pin "86") (pinfunction "C1_86") (pintype "bidirectional"))
    )
    (net (code "114") (name "unconnected-(U3-C2-Pad87)") (class "Default")
      (node (ref "U3") (pin "87") (pinfunction "C2_87") (pintype "bidirectional"))
    )
    (net (code "115") (name "unconnected-(U3-C3-Pad88)") (class "Default")
      (node (ref "U3") (pin "88") (pinfunction "C3_88") (pintype "bidirectional"))
    )
    (net (code "116") (name "unconnected-(U3-C4-Pad9)") (class "Default")
      (node (ref "U3") (pin "9") (pinfunction "C4_9") (pintype "bidirectional"))
    )
    (net (code "117") (name "unconnected-(U3-C13-Pad57)") (class "Default")
      (node (ref "U3") (pin "57") (pinfunction "C13_57") (pintype "bidirectional"))
    )
    (net (code "118") (name "unconnected-(U3-C14-Pad58)") (class "Default")
      (node (ref "U3") (pin "58") (pinfunction "C14_58") (pintype "bidirectional"))
    )
    (net (code "119") (name "unconnected-(U3-D+-Pad96)") (class "Default")
      (node (ref "U3") (pin "96") (pinfunction "D+_96") (pintype "bidirectional"))
    )
    (net (code "120") (name "unconnected-(U3-D--Pad95)") (class "Default")
      (node (ref "U3") (pin "95") (pinfunction "D-_95") (pintype "bidirectional"))
    )
    (net (code "121") (name "unconnected-(U3-D1-Pad59)") (class "Default")
      (node (ref "U3") (pin "59") (pinfunction "D1_59") (pintype "bidirectional"))
    )
    (net (code "122") (name "unconnected-(U3-D2-Pad60)") (class "Default")
      (node (ref "U3") (pin "60") (pinfunction "D2_60") (pintype "bidirectional"))
    )
    (net (code "123") (name "unconnected-(U3-D3-Pad61)") (class "Default")
      (node (ref "U3") (pin "61") (pinfunction "D3_61") (pintype "bidirectional"))
    )
    (net (code "124") (name "unconnected-(U3-D4-Pad64)") (class "Default")
      (node (ref "U3") (pin "64") (pinfunction "D4_64") (pintype "bidirectional"))
    )
    (net (code "125") (name "unconnected-(U3-D5-Pad65)") (class "Default")
      (node (ref "U3") (pin "65") (pinfunction "D5_65") (pintype "bidirectional"))
    )
    (net (code "126") (name "unconnected-(U3-D6-Pad66)") (class "Default")
      (node (ref "U3") (pin "66") (pinfunction "D6_66") (pintype "bidirectional"))
    )
    (net (code "127") (name "unconnected-(U3-D7-Pad67)") (class "Default")
      (node (ref "U3") (pin "67") (pinfunction "D7_67") (pintype "bidirectional"))
    )
    (net (code "128") (name "unconnected-(U3-D8-Pad52)") (class "Default")
      (node (ref "U3") (pin "52") (pinfunction "D8_52") (pintype "bidirectional"))
    )
    (net (code "129") (name "unconnected-(U3-D9-Pad53)") (class "Default")
      (node (ref "U3") (pin "53") (pinfunction "D9_53") (pintype "bidirectional"))
    )
    (net (code "130") (name "unconnected-(U3-D10-Pad54)") (class "Default")
      (node (ref "U3") (pin "54") (pinfunction "D10_54") (pintype "bidirectional"))
    )
    (net (code "131") (name "unconnected-(U3-D11-Pad55)") (class "Default")
      (node (ref "U3") (pin "55") (pinfunction "D11_55") (pintype "bidirectional"))
    )
    (net (code "132") (name "unconnected-(U3-D12-Pad62)") (class "Default")
      (node (ref "U3") (pin "62") (pinfunction "D12_62") (pintype "bidirectional"))
    )
    (net (code "133") (name "unconnected-(U3-D13-Pad63)") (class "Default")
      (node (ref "U3") (pin "63") (pinfunction "D13_63") (pintype "bidirectional"))
    )
    (net (code "134") (name "unconnected-(U3-D14-Pad34)") (class "Default")
      (node (ref "U3") (pin "34") (pinfunction "D14_34") (pintype "bidirectional"))
    )
    (net (code "135") (name "unconnected-(U3-E0-Pad74)") (class "Default")
      (node (ref "U3") (pin "74") (pinfunction "E0_74") (pintype "bidirectional"))
    )
    (net (code "136") (name "unconnected-(U3-E1-Pad75)") (class "Default")
      (node (ref "U3") (pin "75") (pinfunction "E1_75") (pintype "bidirectional"))
    )
    (net (code "137") (name "unconnected-(U3-E2-Pad79)") (class "Default")
      (node (ref "U3") (pin "79") (pinfunction "E2_79") (pintype "bidirectional"))
    )
    (net (code "138") (name "unconnected-(U3-E3-Pad80)") (class "Default")
      (node (ref "U3") (pin "80") (pinfunction "E3_80") (pintype "bidirectional"))
    )
    (net (code "139") (name "unconnected-(U3-E4-Pad81)") (class "Default")
      (node (ref "U3") (pin "81") (pinfunction "E4_81") (pintype "bidirectional"))
    )
    (net (code "140") (name "unconnected-(U3-E5-Pad83)") (class "Default")
      (node (ref "U3") (pin "83") (pinfunction "E5_83") (pintype "bidirectional"))
    )
    (net (code "141") (name "unconnected-(U3-E6-Pad84)") (class "Default")
      (node (ref "U3") (pin "84") (pinfunction "E6_84") (pintype "bidirectional"))
    )
    (net (code "142") (name "unconnected-(U3-E7-Pad85)") (class "Default")
      (node (ref "U3") (pin "85") (pinfunction "E7_85") (pintype "bidirectional"))
    )
    (net (code "143") (name "unconnected-(U3-E8-Pad16)") (class "Default")
      (node (ref "U3") (pin "16") (pinfunction "E8_16") (pintype "bidirectional"))
    )
    (net (code "144") (name "unconnected-(U3-E9-Pad17)") (class "Default")
      (node (ref "U3") (pin "17") (pinfunction "E9_17") (pintype "bidirectional"))
    )
    (net (code "145") (name "unconnected-(U3-F0-Pad68)") (class "Default")
      (node (ref "U3") (pin "68") (pinfunction "F0_68") (pintype "bidirectional"))
    )
    (net (code "146") (name "unconnected-(U3-F1-Pad69)") (class "Default")
      (node (ref "U3") (pin "69") (pinfunction "F1_69") (pintype "bidirectional"))
    )
    (net (code "147") (name "unconnected-(U3-F2-Pad38)") (class "Default")
      (node (ref "U3") (pin "38") (pinfunction "F2_38") (pintype "bidirectional"))
    )
    (net (code "148") (name "unconnected-(U3-F8-Pad39)") (class "Default")
      (node (ref "U3") (pin "39") (pinfunction "F8_39") (pintype "bidirectional"))
    )
    (net (code "149") (name "unconnected-(U3-F12-Pad29)") (class "Default")
      (node (ref "U3") (pin "29") (pinfunction "F12_29") (pintype "bidirectional"))
    )
    (net (code "150") (name "unconnected-(U3-F13-Pad28)") (class "Default")
      (node (ref "U3") (pin "28") (pinfunction "F13_28") (pintype "bidirectional"))
    )
    (net (code "151") (name "unconnected-(U3-G0-Pad71)") (class "Default")
      (node (ref "U3") (pin "71") (pinfunction "G0_71") (pintype "bidirectional"))
    )
    (net (code "152") (name "unconnected-(U3-G1-Pad70)") (class "Default")
      (node (ref "U3") (pin "70") (pinfunction "G1_70") (pintype "bidirectional"))
    )
    (net (code "153") (name "unconnected-(U3-G6-Pad10)") (class "Default")
      (node (ref "U3") (pin "10") (pinfunction "G6_10") (pintype "bidirectional"))
    )
    (net (code "154") (name "unconnected-(U3-G7-Pad11)") (class "Default")
      (node (ref "U3") (pin "11") (pinfunction "G7_11") (pintype "bidirectional"))
    )
    (net (code "155") (name "unconnected-(U3-G8-Pad12)") (class "Default")
      (node (ref "U3") (pin "12") (pinfunction "G8_12") (pintype "bidirectional"))
    )
    (net (code "156") (name "unconnected-(U3-G9-Pad14)") (class "Default")
      (node (ref "U3") (pin "14") (pinfunction "G9_14") (pintype "bidirectional"))
    )
    (net (code "157") (name "unconnected-(U3-G12-Pad77)") (class "Default")
      (node (ref "U3") (pin "77") (pinfunction "G12_77") (pintype "bidirectional"))
    )
    (net (code "158") (name "unconnected-(U3-G13-Pad78)") (class "Default")
      (node (ref "U3") (pin "78") (pinfunction "G13_78") (pintype "bidirectional"))
    )
    (net (code "159") (name "unconnected-(U3-G14-Pad76)") (class "Default")
      (node (ref "U3") (pin "76") (pinfunction "G14_76") (pintype "bidirectional"))
    )
    (net (code "160") (name "unconnected-(U3-G15-Pad82)") (class "Default")
      (node (ref "U3") (pin "82") (pinfunction "G15_82") (pintype "bidirectional"))
    )
    (net (code "161") (name "unconnected-(U3-HOST1-Pad92)") (class "Default")
      (node (ref "U3") (pin "92") (pinfunction "HOST1_92") (pintype "bidirectional"))
    )
    (net (code "162") (name "unconnected-(U3-HOST2-Pad93)") (class "Default")
      (node (ref "U3") (pin "93") (pinfunction "HOST2_93") (pintype "bidirectional"))
    )
    (net (code "163") (name "unconnected-(U3-ID-Pad97)") (class "Default")
      (node (ref "U3") (pin "97") (pinfunction "ID_97") (pintype "bidirectional"))
    )
    (net (code "164") (name "unconnected-(U3-VPP2-Pad13)") (class "Default")
      (node (ref "U3") (pin "13") (pinfunction "VPP2_13") (pintype "input"))
    )
    (net (code "165") (name "unconnected-(U4-HV4-PadP$7)") (class "Default")
      (node (ref "U4") (pin "P$7") (pinfunction "HV4_P$7") (pintype "bidirectional"))
    )
  )
)
